# SCH_Placa-PCB_-_Juan_Pablo_Fuentes.net
KiCad netlist of a schematic drawn in EasyEDA
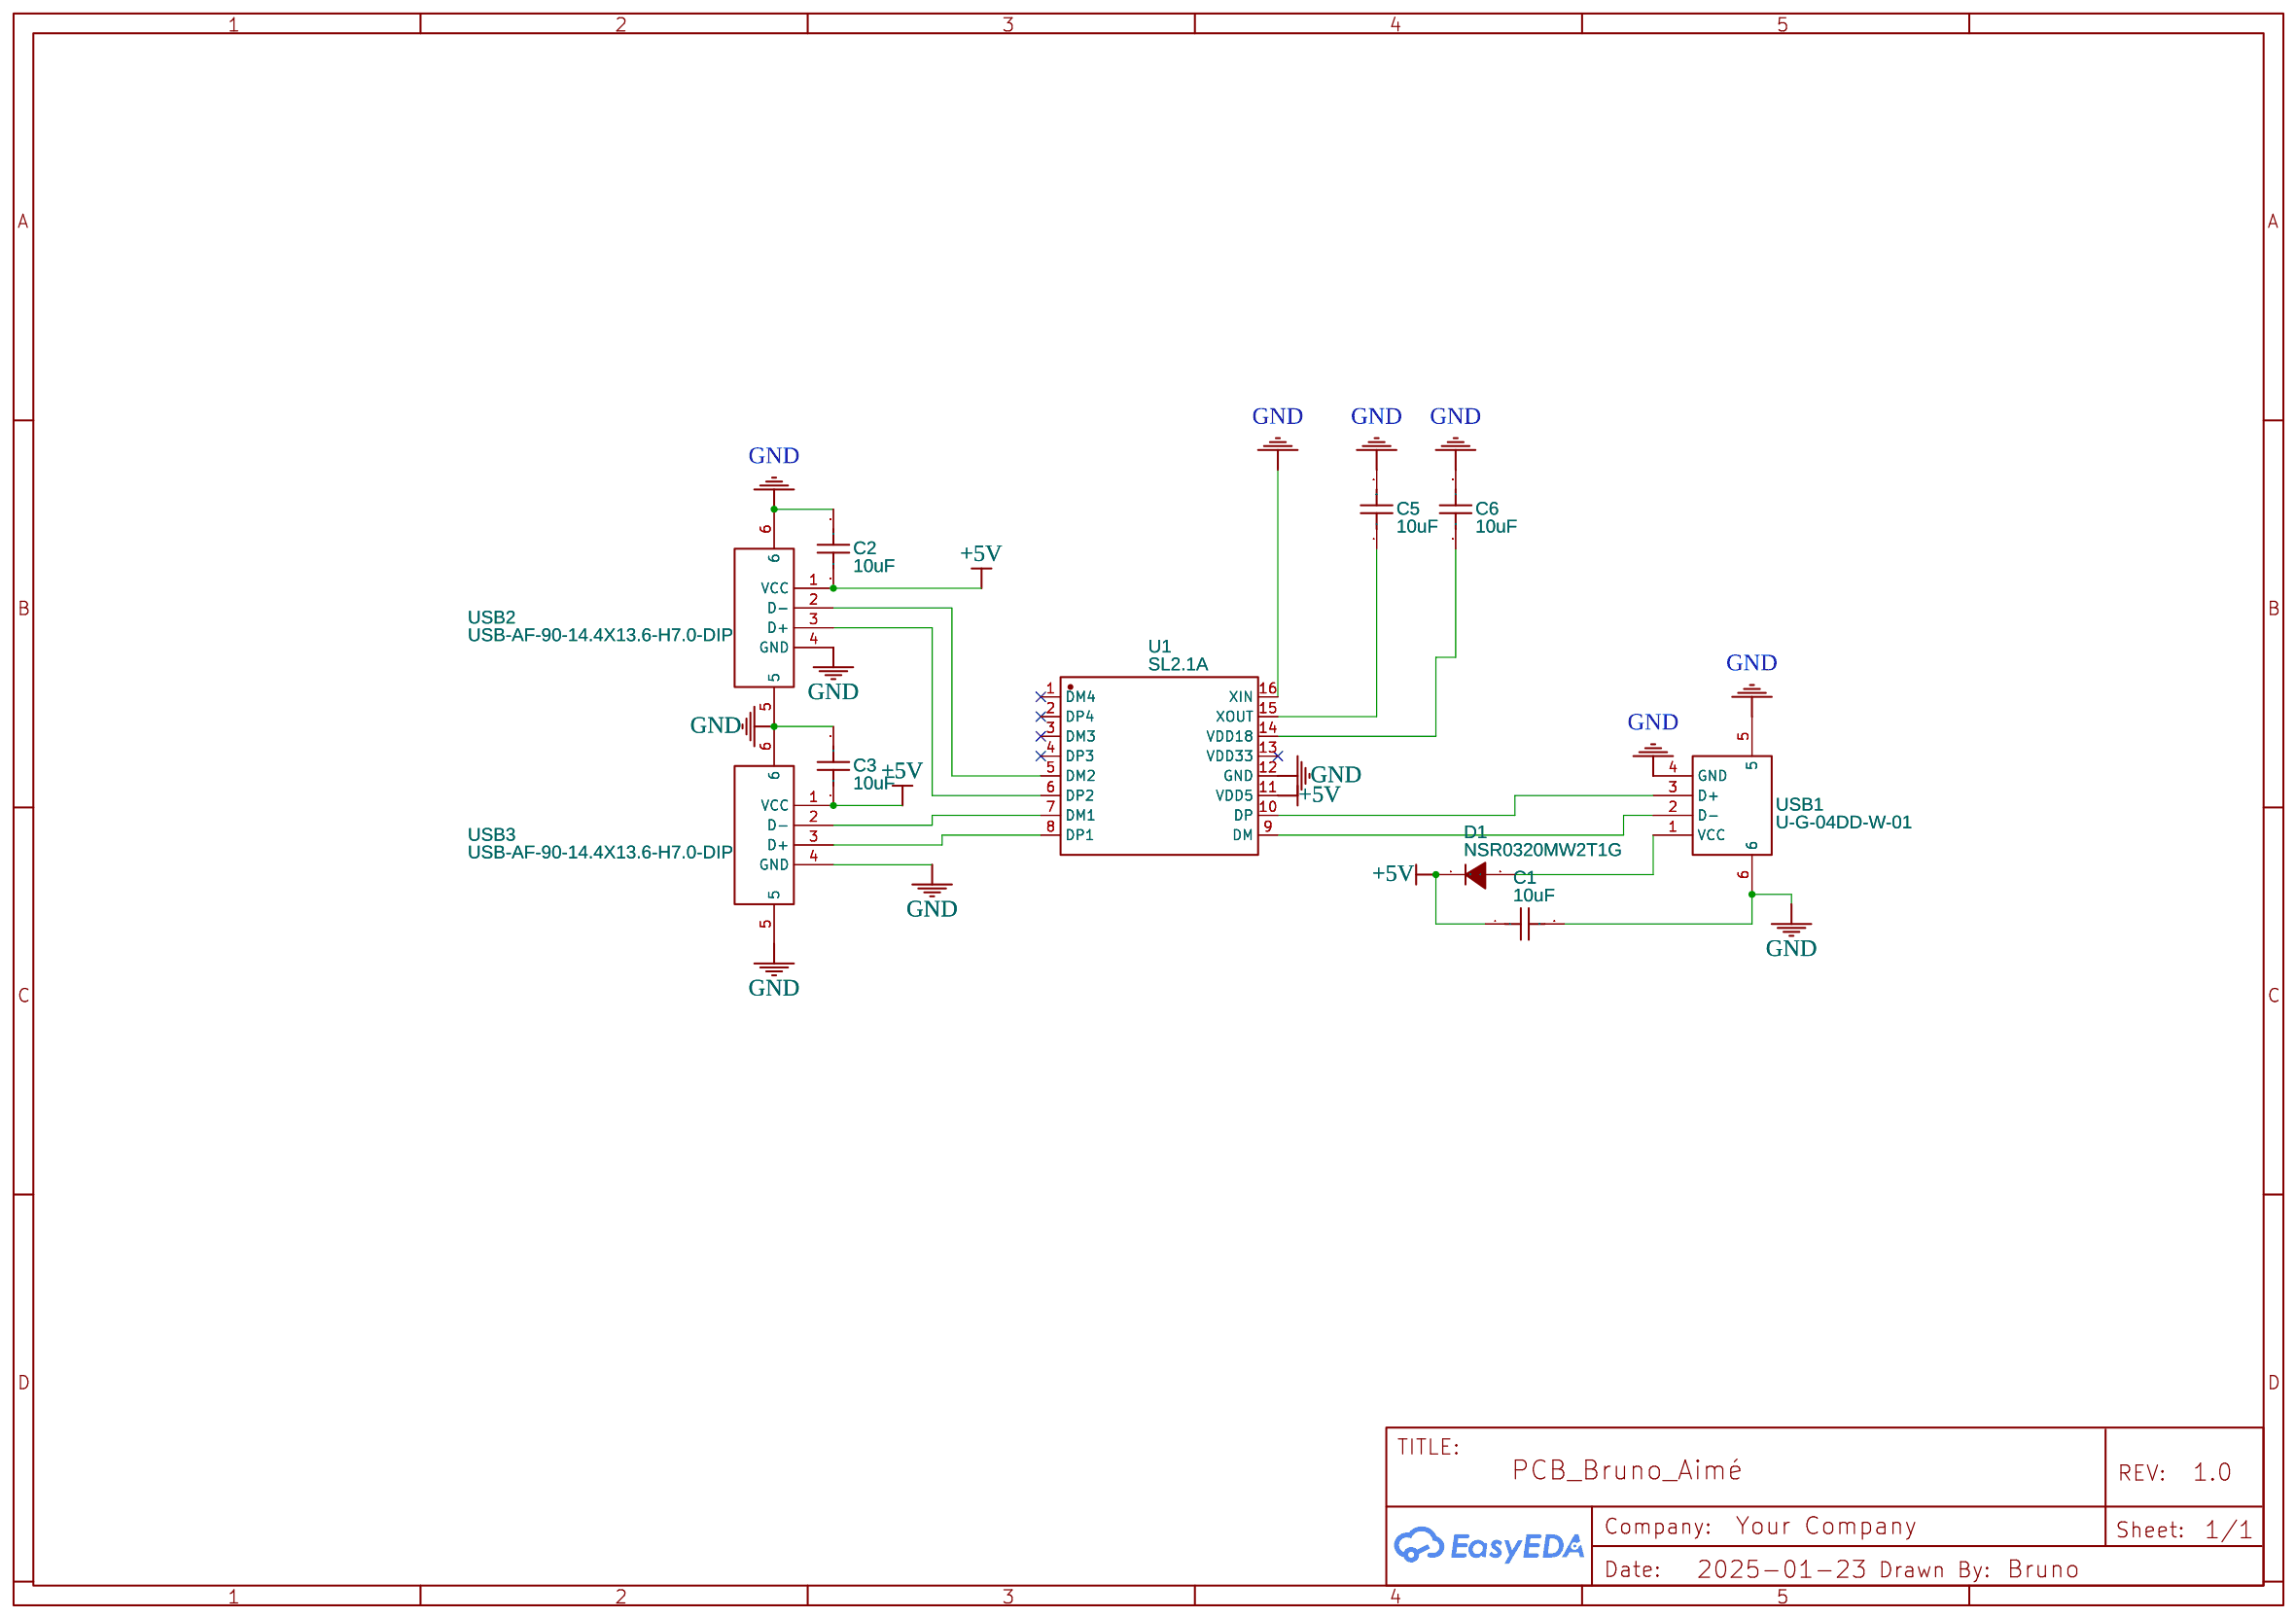
[diagram p0: schematic sheet]

(export (version "E")
  (design (tool "Eeschema 10.0.6"))
  (components
    (comp (ref "C1")
      (value "10uF")
      (fields
        (field (name "Manufacturer Part") "CL10A106KP8NNNC")
        (field (name "Manufacturer") "SAMSUNG(三星)")
      )
      (libsource (lib "") (part "CL10A106KP8NNNC"))
    )
    (comp (ref "C2")
      (value "10uF")
      (fields
        (field (name "Manufacturer Part") "CL10A106KP8NNNC")
        (field (name "Manufacturer") "SAMSUNG(三星)")
      )
      (libsource (lib "") (part "CL10A106KP8NNNC_1"))
    )
    (comp (ref "C3")
      (value "10uF")
      (fields
        (field (name "Manufacturer Part") "CL10A106KP8NNNC")
        (field (name "Manufacturer") "SAMSUNG(三星)")
      )
      (libsource (lib "") (part "CL10A106KP8NNNC_1"))
    )
    (comp (ref "C5")
      (value "10uF")
      (fields
        (field (name "Manufacturer Part") "CL10A106KP8NNNC")
        (field (name "Manufacturer") "SAMSUNG(三星)")
      )
      (libsource (lib "") (part "CL10A106KP8NNNC_1"))
    )
    (comp (ref "C6")
      (value "10uF")
      (fields
        (field (name "Manufacturer Part") "CL10A106KP8NNNC")
        (field (name "Manufacturer") "SAMSUNG(三星)")
      )
      (libsource (lib "") (part "CL10A106KP8NNNC_1"))
    )
    (comp (ref "D1")
      (value "NSR0320MW2T1G")
      (fields (field (name "Manufacturer") "onsemi(安森美)"))
      (libsource (lib "") (part "NSR0320MW2T1G"))
    )
    (comp (ref "U1")
      (value "SL2.1A")
      (fields (field (name "Manufacturer") "CoreChips(和芯润德)"))
      (libsource (lib "") (part "SL2.1A"))
    )
    (comp (ref "USB1")
      (value "U-G-04DD-W-01")
      (fields (field (name "Manufacturer Part") "U-G-O4DD-W-1") (field (name "Manufacturer") "韩国韩荣"))
      (libsource (lib "") (part "U-G-04DD-W-01"))
    )
    (comp (ref "USB2")
      (value "USB-AF-90-14.4X13.6-H7.0-DIP")
      (fields (field (name "Manufacturer Part") "903-131A1011D10100") (field (name "Manufacturer") "精拓金"))
      (libsource (lib "") (part "USB-AF-90-14.4X13.6-H7.0-DIP"))
    )
    (comp (ref "USB3")
      (value "USB-AF-90-14.4X13.6-H7.0-DIP")
      (fields (field (name "Manufacturer Part") "903-131A1011D10100") (field (name "Manufacturer") "精拓金"))
      (libsource (lib "") (part "USB-AF-90-14.4X13.6-H7.0-DIP"))
    )
  )
  (nets
    (net (code "1") (name "+5V") (class "Default")
      (node (ref "C1") (pin "1") (pinfunction "1_1") (pintype "unspecified"))
      (node (ref "C2") (pin "1") (pinfunction "1_1") (pintype "unspecified"))
      (node (ref "C3") (pin "1") (pinfunction "1_1") (pintype "unspecified"))
      (node (ref "D1") (pin "1") (pinfunction "C_1") (pintype "unspecified"))
      (node (ref "U1") (pin "11") (pinfunction "VDD5_11") (pintype "unspecified"))
      (node (ref "USB2") (pin "1") (pinfunction "VCC_1") (pintype "unspecified"))
      (node (ref "USB3") (pin "1") (pinfunction "VCC_1") (pintype "unspecified"))
    )
    (net (code "2") (name "GND") (class "Default")
      (node (ref "C1") (pin "2") (pinfunction "2_2") (pintype "unspecified"))
      (node (ref "C2") (pin "2") (pinfunction "2_2") (pintype "unspecified"))
      (node (ref "C3") (pin "2") (pinfunction "2_2") (pintype "unspecified"))
      (node (ref "C5") (pin "2") (pinfunction "2_2") (pintype "unspecified"))
      (node (ref "C6") (pin "2") (pinfunction "2_2") (pintype "unspecified"))
      (node (ref "U1") (pin "12") (pinfunction "GND_12") (pintype "unspecified"))
      (node (ref "U1") (pin "16") (pinfunction "XIN_16") (pintype "unspecified"))
      (node (ref "USB1") (pin "4") (pinfunction "GND_4") (pintype "unspecified"))
      (node (ref "USB1") (pin "5") (pinfunction "5_5") (pintype "unspecified"))
      (node (ref "USB1") (pin "6") (pinfunction "6_6") (pintype "unspecified"))
      (node (ref "USB2") (pin "4") (pinfunction "GND_4") (pintype "unspecified"))
      (node (ref "USB2") (pin "5") (pinfunction "5_5") (pintype "unspecified"))
      (node (ref "USB2") (pin "6") (pinfunction "6_6") (pintype "unspecified"))
      (node (ref "USB3") (pin "4") (pinfunction "GND_4") (pintype "unspecified"))
      (node (ref "USB3") (pin "5") (pinfunction "5_5") (pintype "unspecified"))
      (node (ref "USB3") (pin "6") (pinfunction "6_6") (pintype "unspecified"))
    )
    (net (code "3") (name "Net-(D1-A)") (class "Default")
      (node (ref "D1") (pin "2") (pinfunction "A_2") (pintype "unspecified"))
      (node (ref "USB1") (pin "1") (pinfunction "VCC_1") (pintype "unspecified"))
    )
    (net (code "4") (name "Net-(U1-DM)") (class "Default")
      (node (ref "U1") (pin "9") (pinfunction "DM_9") (pintype "unspecified"))
      (node (ref "USB1") (pin "2") (pinfunction "D-_2") (pintype "unspecified"))
    )
    (net (code "5") (name "Net-(U1-DM1)") (class "Default")
      (node (ref "U1") (pin "7") (pinfunction "DM1_7") (pintype "unspecified"))
      (node (ref "USB3") (pin "2") (pinfunction "D-_2") (pintype "unspecified"))
    )
    (net (code "6") (name "Net-(U1-DM2)") (class "Default")
      (node (ref "U1") (pin "5") (pinfunction "DM2_5") (pintype "unspecified"))
      (node (ref "USB2") (pin "2") (pinfunction "D-_2") (pintype "unspecified"))
    )
    (net (code "7") (name "Net-(U1-DP)") (class "Default")
      (node (ref "U1") (pin "10") (pinfunction "DP_10") (pintype "unspecified"))
      (node (ref "USB1") (pin "3") (pinfunction "D+_3") (pintype "unspecified"))
    )
    (net (code "8") (name "Net-(U1-DP1)") (class "Default")
      (node (ref "U1") (pin "8") (pinfunction "DP1_8") (pintype "unspecified"))
      (node (ref "USB3") (pin "3") (pinfunction "D+_3") (pintype "unspecified"))
    )
    (net (code "9") (name "Net-(U1-DP2)") (class "Default")
      (node (ref "U1") (pin "6") (pinfunction "DP2_6") (pintype "unspecified"))
      (node (ref "USB2") (pin "3") (pinfunction "D+_3") (pintype "unspecified"))
    )
    (net (code "10") (name "Net-(U1-VDD18)") (class "Default")
      (node (ref "C6") (pin "1") (pinfunction "1_1") (pintype "unspecified"))
      (node (ref "U1") (pin "14") (pinfunction "VDD18_14") (pintype "unspecified"))
    )
    (net (code "11") (name "Net-(U1-XOUT)") (class "Default")
      (node (ref "C5") (pin "1") (pinfunction "1_1") (pintype "unspecified"))
      (node (ref "U1") (pin "15") (pinfunction "XOUT_15") (pintype "unspecified"))
    )
    (net (code "12") (name "unconnected-(U1-DM3-Pad3)") (class "Default")
      (node (ref "U1") (pin "3") (pinfunction "DM3_3") (pintype "unspecified+no_connect"))
    )
    (net (code "13") (name "unconnected-(U1-DM4-Pad1)") (class "Default")
      (node (ref "U1") (pin "1") (pinfunction "DM4_1") (pintype "unspecified+no_connect"))
    )
    (net (code "14") (name "unconnected-(U1-DP3-Pad4)") (class "Default")
      (node (ref "U1") (pin "4") (pinfunction "DP3_4") (pintype "unspecified+no_connect"))
    )
    (net (code "15") (name "unconnected-(U1-DP4-Pad2)") (class "Default")
      (node (ref "U1") (pin "2") (pinfunction "DP4_2") (pintype "unspecified+no_connect"))
    )
    (net (code "16") (name "unconnected-(U1-VDD33-Pad13)") (class "Default")
      (node (ref "U1") (pin "13") (pinfunction "VDD33_13") (pintype "unspecified+no_connect"))
    )
  )
)
